# NewBee.net
KiCad netlist of a schematic drawn in Altium Designer
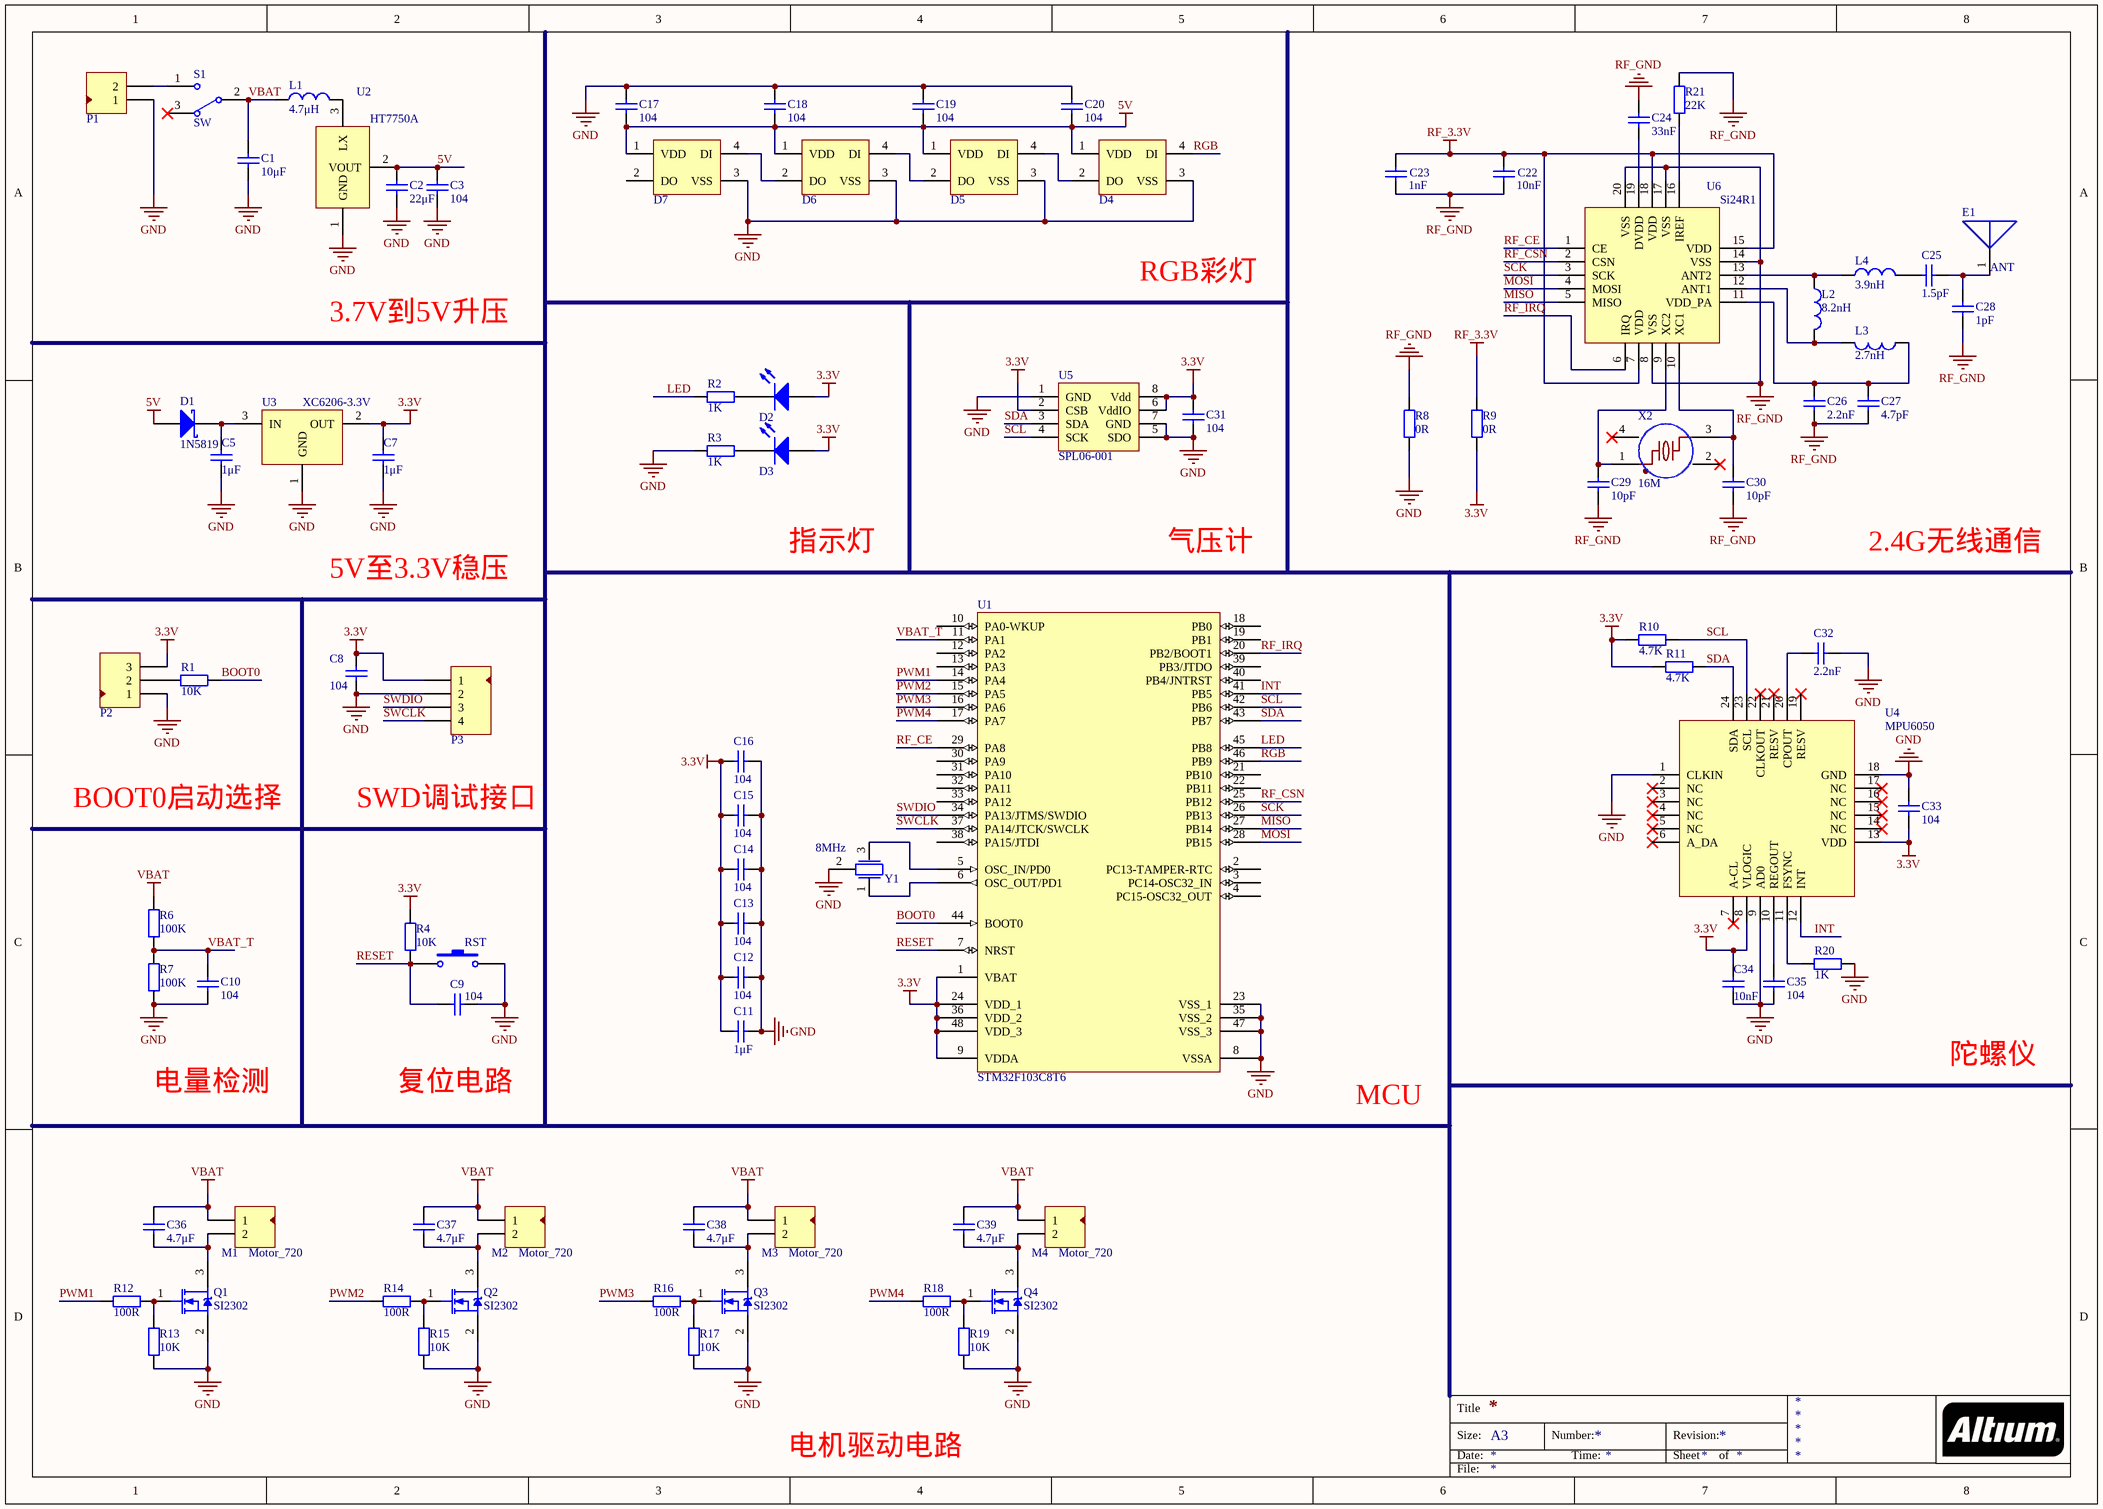
[diagram p0: NewBee.SchDoc]

(export (version "E")
  (design (tool "Eeschema 10.0.6"))
  (components
    (comp (ref "C1")
      (value "10μF")
      (footprint "C-0603")
      (description "贴片瓷片电容")
      (fields (field (name "PUBLISHER") "Altium Limited"))
      (libsource (lib "ChunLee") (part "Cap-S"))
    )
    (comp (ref "C2")
      (value "22μF")
      (footprint "C-0603")
      (description "贴片瓷片电容")
      (fields (field (name "PUBLISHER") "Altium Limited"))
      (libsource (lib "ChunLee") (part "Cap-S"))
    )
    (comp (ref "C3")
      (value "104")
      (footprint "C-0603")
      (description "贴片瓷片电容")
      (fields (field (name "PUBLISHER") "Altium Limited"))
      (libsource (lib "ChunLee") (part "Cap-S"))
    )
    (comp (ref "C5")
      (value "1μF")
      (footprint "C-0603")
      (description "贴片瓷片电容")
      (fields (field (name "PUBLISHER") "Altium Limited"))
      (libsource (lib "ChunLee") (part "Cap-S"))
    )
    (comp (ref "C7")
      (value "1μF")
      (footprint "C-0603")
      (description "贴片瓷片电容")
      (fields (field (name "PUBLISHER") "Altium Limited"))
      (libsource (lib "ChunLee") (part "Cap-S"))
    )
    (comp (ref "C8")
      (value "104")
      (footprint "C-0603")
      (description "贴片瓷片电容")
      (fields (field (name "PUBLISHER") "Altium Limited"))
      (libsource (lib "ChunLee") (part "Cap-S"))
    )
    (comp (ref "C9")
      (value "104")
      (footprint "C-0603")
      (description "贴片瓷片电容")
      (fields (field (name "PUBLISHER") "Altium Limited"))
      (libsource (lib "ChunLee") (part "Cap-S"))
    )
    (comp (ref "C10")
      (value "104")
      (footprint "C-0603")
      (description "贴片瓷片电容")
      (fields (field (name "PUBLISHER") "Altium Limited"))
      (libsource (lib "ChunLee") (part "Cap-S"))
    )
    (comp (ref "C11")
      (value "1μF")
      (footprint "C-0603")
      (description "贴片瓷片电容")
      (fields (field (name "PUBLISHER") "Altium Limited"))
      (libsource (lib "ChunLee") (part "Cap-S"))
    )
    (comp (ref "C12")
      (value "104")
      (footprint "C-0603")
      (description "贴片瓷片电容")
      (fields (field (name "PUBLISHER") "Altium Limited"))
      (libsource (lib "ChunLee") (part "Cap-S"))
    )
    (comp (ref "C13")
      (value "104")
      (footprint "C-0603")
      (description "贴片瓷片电容")
      (fields (field (name "PUBLISHER") "Altium Limited"))
      (libsource (lib "ChunLee") (part "Cap-S"))
    )
    (comp (ref "C14")
      (value "104")
      (footprint "C-0603")
      (description "贴片瓷片电容")
      (fields (field (name "PUBLISHER") "Altium Limited"))
      (libsource (lib "ChunLee") (part "Cap-S"))
    )
    (comp (ref "C15")
      (value "104")
      (footprint "C-0603")
      (description "贴片瓷片电容")
      (fields (field (name "PUBLISHER") "Altium Limited"))
      (libsource (lib "ChunLee") (part "Cap-S"))
    )
    (comp (ref "C16")
      (value "104")
      (footprint "C-0603")
      (description "贴片瓷片电容")
      (fields (field (name "PUBLISHER") "Altium Limited"))
      (libsource (lib "ChunLee") (part "Cap-S"))
    )
    (comp (ref "C17")
      (value "104")
      (footprint "C-0603")
      (description "贴片瓷片电容")
      (fields (field (name "PUBLISHER") "Altium Limited"))
      (libsource (lib "ChunLee") (part "Cap-S"))
    )
    (comp (ref "C18")
      (value "104")
      (footprint "C-0603")
      (description "贴片瓷片电容")
      (fields (field (name "PUBLISHER") "Altium Limited"))
      (libsource (lib "ChunLee") (part "Cap-S"))
    )
    (comp (ref "C19")
      (value "104")
      (footprint "C-0603")
      (description "贴片瓷片电容")
      (fields (field (name "PUBLISHER") "Altium Limited"))
      (libsource (lib "ChunLee") (part "Cap-S"))
    )
    (comp (ref "C20")
      (value "104")
      (footprint "C-0603")
      (description "贴片瓷片电容")
      (fields (field (name "PUBLISHER") "Altium Limited"))
      (libsource (lib "ChunLee") (part "Cap-S"))
    )
    (comp (ref "C22")
      (value "10nF")
      (footprint "C-0603")
      (description "贴片瓷片电容")
      (fields (field (name "PUBLISHER") "Altium Limited"))
      (libsource (lib "ChunLee") (part "Cap-S"))
    )
    (comp (ref "C23")
      (value "1nF")
      (footprint "C-0603")
      (description "贴片瓷片电容")
      (fields (field (name "PUBLISHER") "Altium Limited"))
      (libsource (lib "ChunLee") (part "Cap-S"))
    )
    (comp (ref "C24")
      (value "33nF")
      (footprint "C-0603")
      (description "贴片瓷片电容")
      (fields (field (name "PUBLISHER") "Altium Limited"))
      (libsource (lib "ChunLee") (part "Cap-S"))
    )
    (comp (ref "C25")
      (value "1.5pF")
      (footprint "C-0603")
      (description "贴片瓷片电容")
      (fields (field (name "PUBLISHER") "Altium Limited"))
      (libsource (lib "ChunLee") (part "Cap-S"))
    )
    (comp (ref "C26")
      (value "2.2nF")
      (footprint "C-0603")
      (description "贴片瓷片电容")
      (fields (field (name "PUBLISHER") "Altium Limited"))
      (libsource (lib "ChunLee") (part "Cap-S"))
    )
    (comp (ref "C27")
      (value "4.7pF")
      (footprint "C-0603")
      (description "贴片瓷片电容")
      (fields (field (name "PUBLISHER") "Altium Limited"))
      (libsource (lib "ChunLee") (part "Cap-S"))
    )
    (comp (ref "C28")
      (value "1pF")
      (footprint "C-0603")
      (description "贴片瓷片电容")
      (fields (field (name "PUBLISHER") "Altium Limited"))
      (libsource (lib "ChunLee") (part "Cap-S"))
    )
    (comp (ref "C29")
      (value "10pF")
      (footprint "C-0603")
      (description "贴片瓷片电容")
      (fields (field (name "PUBLISHER") "Altium Limited"))
      (libsource (lib "ChunLee") (part "Cap-S"))
    )
    (comp (ref "C30")
      (value "10pF")
      (footprint "C-0603")
      (description "贴片瓷片电容")
      (fields (field (name "PUBLISHER") "Altium Limited"))
      (libsource (lib "ChunLee") (part "Cap-S"))
    )
    (comp (ref "C31")
      (value "104")
      (footprint "C-0603")
      (description "贴片瓷片电容")
      (fields (field (name "PUBLISHER") "Altium Limited"))
      (libsource (lib "ChunLee") (part "Cap-S"))
    )
    (comp (ref "C32")
      (value "2.2nF")
      (footprint "C-0603")
      (description "贴片瓷片电容")
      (fields (field (name "PUBLISHER") "Altium Limited"))
      (libsource (lib "ChunLee") (part "Cap-S"))
    )
    (comp (ref "C33")
      (value "104")
      (footprint "C-0603")
      (description "贴片瓷片电容")
      (fields (field (name "PUBLISHER") "Altium Limited"))
      (libsource (lib "ChunLee") (part "Cap-S"))
    )
    (comp (ref "C34")
      (value "10nF")
      (footprint "C-0603")
      (description "贴片瓷片电容")
      (fields (field (name "PUBLISHER") "Altium Limited"))
      (libsource (lib "ChunLee") (part "Cap-S"))
    )
    (comp (ref "C35")
      (value "104")
      (footprint "C-0603")
      (description "贴片瓷片电容")
      (fields (field (name "PUBLISHER") "Altium Limited"))
      (libsource (lib "ChunLee") (part "Cap-S"))
    )
    (comp (ref "C36")
      (value "4.7μF")
      (footprint "C-0603")
      (description "贴片瓷片电容")
      (fields (field (name "PUBLISHER") "Altium Limited"))
      (libsource (lib "ChunLee") (part "Cap-S"))
    )
    (comp (ref "C37")
      (value "4.7μF")
      (footprint "C-0603")
      (description "贴片瓷片电容")
      (fields (field (name "PUBLISHER") "Altium Limited"))
      (libsource (lib "ChunLee") (part "Cap-S"))
    )
    (comp (ref "C38")
      (value "4.7μF")
      (footprint "C-0603")
      (description "贴片瓷片电容")
      (fields (field (name "PUBLISHER") "Altium Limited"))
      (libsource (lib "ChunLee") (part "Cap-S"))
    )
    (comp (ref "C39")
      (value "4.7μF")
      (footprint "C-0603")
      (description "贴片瓷片电容")
      (fields (field (name "PUBLISHER") "Altium Limited"))
      (libsource (lib "ChunLee") (part "Cap-S"))
    )
    (comp (ref "D1")
      (value "1N5819")
      (footprint "SOD-323_L1.6-W1.3-LS2.7-RD")
      (description "肖特基二极管")
      (fields (field (name "TYPE") "1N5819") (field (name "PUBLISHER") "Altium Limited"))
      (libsource (lib "ChunLee") (part "Diode-Schottky"))
    )
    (comp (ref "D2")
      (value "LED0")
      (footprint "LED-0805")
      (description "发光二极管")
      (fields (field (name "PUBLISHER") "Altium Limited"))
      (libsource (lib "ChunLee") (part "LED0"))
    )
    (comp (ref "D3")
      (value "LED0")
      (footprint "LED-0805")
      (description "发光二极管")
      (fields (field (name "PUBLISHER") "Altium Limited"))
      (libsource (lib "ChunLee") (part "LED0"))
    )
    (comp (ref "D4")
      (value "WS2812B")
      (footprint "SMD-5050-4")
      (description "WS2812B 4脚RGB全彩LED")
      (libsource (lib "ChunLee") (part "WS2812B"))
    )
    (comp (ref "D5")
      (value "WS2812B")
      (footprint "SMD-5050-4")
      (description "WS2812B 4脚RGB全彩LED")
      (libsource (lib "ChunLee") (part "WS2812B"))
    )
    (comp (ref "D6")
      (value "WS2812B")
      (footprint "SMD-5050-4")
      (description "WS2812B 4脚RGB全彩LED")
      (libsource (lib "ChunLee") (part "WS2812B"))
    )
    (comp (ref "D7")
      (value "WS2812B")
      (footprint "SMD-5050-4")
      (description "WS2812B 4脚RGB全彩LED")
      (libsource (lib "ChunLee") (part "WS2812B"))
    )
    (comp (ref "E1")
      (value "ANT")
      (footprint "NewBee_PcbLib:AN3216")
      (description "2.4G Antenna")
      (fields (field (name "PUBLISHER") "mazhongwei"))
      (libsource (lib "NewBee_Schlib") (part "ANT"))
    )
    (comp (ref "L1")
      (value "4.7μH")
      (footprint "1210")
      (description "电感")
      (fields (field (name "Comment") "Inductor") (field (name "PUBLISHER") "Altium Limited"))
      (libsource (lib "ChunLee") (part "Inductor"))
    )
    (comp (ref "L2")
      (value "8.2nH")
      (footprint "0603-1")
      (description "电感")
      (fields (field (name "Comment") "Inductor") (field (name "PUBLISHER") "Altium Limited"))
      (libsource (lib "ChunLee") (part "Inductor"))
    )
    (comp (ref "L3")
      (value "2.7nH")
      (footprint "0603-1")
      (description "电感")
      (fields (field (name "Comment") "Inductor") (field (name "PUBLISHER") "Altium Limited"))
      (libsource (lib "ChunLee") (part "Inductor"))
    )
    (comp (ref "L4")
      (value "3.9nH")
      (footprint "0603-1")
      (description "电感")
      (fields (field (name "Comment") "Inductor") (field (name "PUBLISHER") "Altium Limited"))
      (libsource (lib "ChunLee") (part "Inductor"))
    )
    (comp (ref "M1")
      (value "Motor_720")
      (footprint "PH2.0-2P-TH")
      (description "接插件")
      (fields (field (name "PUBLISHER") "Altium Limited"))
      (libsource (lib "HDR_ChunLee") (part "Header 2"))
    )
    (comp (ref "M2")
      (value "Motor_720")
      (footprint "PH2.0-2P-TH")
      (description "接插件")
      (fields (field (name "PUBLISHER") "Altium Limited"))
      (libsource (lib "HDR_ChunLee") (part "Header 2"))
    )
    (comp (ref "M3")
      (value "Motor_720")
      (footprint "PH2.0-2P-TH")
      (description "接插件")
      (fields (field (name "PUBLISHER") "Altium Limited"))
      (libsource (lib "HDR_ChunLee") (part "Header 2"))
    )
    (comp (ref "M4")
      (value "Motor_720")
      (footprint "PH2.0-2P-TH")
      (description "接插件")
      (fields (field (name "PUBLISHER") "Altium Limited"))
      (libsource (lib "HDR_ChunLee") (part "Header 2"))
    )
    (comp (ref "P1")
      (value "Header 2")
      (footprint "PH2.0-2P-SMD-WT")
      (description "接插件")
      (fields (field (name "PUBLISHER") "Altium Limited"))
      (libsource (lib "") (part "Header 2_1"))
    )
    (comp (ref "P2")
      (value "Header 3")
      (footprint "HDR3X1-2.54")
      (description "接插件")
      (fields (field (name "PUBLISHER") "Altium Limited"))
      (libsource (lib "HDR_ChunLee") (part "Header 3"))
    )
    (comp (ref "P3")
      (value "Header 4")
      (footprint "HDR4X1-2.54")
      (description "接插件")
      (fields (field (name "PUBLISHER") "Altium Limited"))
      (libsource (lib "HDR_ChunLee") (part "Header 4"))
    )
    (comp (ref "Q1")
      (value "SI2302")
      (footprint "SOT23-3")
      (description "N沟道贴片")
      (fields (field (name "PUBLISHER") "Altium Limited"))
      (libsource (lib "ChunLee") (part "SI2302"))
    )
    (comp (ref "Q2")
      (value "SI2302")
      (footprint "SOT23-3")
      (description "N沟道贴片")
      (fields (field (name "PUBLISHER") "Altium Limited"))
      (libsource (lib "ChunLee") (part "SI2302"))
    )
    (comp (ref "Q3")
      (value "SI2302")
      (footprint "SOT23-3")
      (description "N沟道贴片")
      (fields (field (name "PUBLISHER") "Altium Limited"))
      (libsource (lib "ChunLee") (part "SI2302"))
    )
    (comp (ref "Q4")
      (value "SI2302")
      (footprint "SOT23-3")
      (description "N沟道贴片")
      (fields (field (name "PUBLISHER") "Altium Limited"))
      (libsource (lib "ChunLee") (part "SI2302"))
    )
    (comp (ref "R1")
      (value "10K")
      (footprint "0603-1")
      (description "贴片电阻")
      (fields (field (name "PUBLISHER") "Altium Limited"))
      (libsource (lib "") (part "Res1_3"))
    )
    (comp (ref "R2")
      (value "1K")
      (footprint "0603-1")
      (description "贴片电阻")
      (fields (field (name "PUBLISHER") "Altium Limited"))
      (libsource (lib "") (part "Res1_2"))
    )
    (comp (ref "R3")
      (value "1K")
      (footprint "0603-1")
      (description "贴片电阻")
      (fields (field (name "PUBLISHER") "Altium Limited"))
      (libsource (lib "") (part "Res1_2"))
    )
    (comp (ref "R4")
      (value "10K")
      (footprint "0603-1")
      (description "贴片电阻")
      (fields (field (name "PUBLISHER") "Altium Limited"))
      (libsource (lib "ChunLee") (part "Res1"))
    )
    (comp (ref "R6")
      (value "100K")
      (footprint "0603-1")
      (description "贴片电阻")
      (fields (field (name "PUBLISHER") "Altium Limited"))
      (libsource (lib "") (part "Res1_1"))
    )
    (comp (ref "R7")
      (value "100K")
      (footprint "0603-1")
      (description "贴片电阻")
      (fields (field (name "PUBLISHER") "Altium Limited"))
      (libsource (lib "") (part "Res1_1"))
    )
    (comp (ref "R8")
      (value "0R")
      (footprint "0603-1")
      (description "贴片电阻")
      (fields (field (name "PUBLISHER") "Altium Limited"))
      (libsource (lib "") (part "Res1_1"))
    )
    (comp (ref "R9")
      (value "0R")
      (footprint "0603-1")
      (description "贴片电阻")
      (fields (field (name "PUBLISHER") "Altium Limited"))
      (libsource (lib "") (part "Res1_1"))
    )
    (comp (ref "R10")
      (value "4.7K")
      (footprint "0603-1")
      (description "贴片电阻")
      (fields (field (name "PUBLISHER") "Altium Limited"))
      (libsource (lib "") (part "Res1_2"))
    )
    (comp (ref "R11")
      (value "4.7K")
      (footprint "0603-1")
      (description "贴片电阻")
      (fields (field (name "PUBLISHER") "Altium Limited"))
      (libsource (lib "") (part "Res1_2"))
    )
    (comp (ref "R12")
      (value "100R")
      (footprint "0603-1")
      (description "贴片电阻")
      (fields (field (name "PUBLISHER") "Altium Limited"))
      (libsource (lib "") (part "Res1_2"))
    )
    (comp (ref "R13")
      (value "10K")
      (footprint "0603-1")
      (description "贴片电阻")
      (fields (field (name "PUBLISHER") "Altium Limited"))
      (libsource (lib "ChunLee") (part "Res1"))
    )
    (comp (ref "R14")
      (value "100R")
      (footprint "0603-1")
      (description "贴片电阻")
      (fields (field (name "PUBLISHER") "Altium Limited"))
      (libsource (lib "") (part "Res1_2"))
    )
    (comp (ref "R15")
      (value "10K")
      (footprint "0603-1")
      (description "贴片电阻")
      (fields (field (name "PUBLISHER") "Altium Limited"))
      (libsource (lib "ChunLee") (part "Res1"))
    )
    (comp (ref "R16")
      (value "100R")
      (footprint "0603-1")
      (description "贴片电阻")
      (fields (field (name "PUBLISHER") "Altium Limited"))
      (libsource (lib "") (part "Res1_2"))
    )
    (comp (ref "R17")
      (value "10K")
      (footprint "0603-1")
      (description "贴片电阻")
      (fields (field (name "PUBLISHER") "Altium Limited"))
      (libsource (lib "ChunLee") (part "Res1"))
    )
    (comp (ref "R18")
      (value "100R")
      (footprint "0603-1")
      (description "贴片电阻")
      (fields (field (name "PUBLISHER") "Altium Limited"))
      (libsource (lib "") (part "Res1_2"))
    )
    (comp (ref "R19")
      (value "10K")
      (footprint "0603-1")
      (description "贴片电阻")
      (fields (field (name "PUBLISHER") "Altium Limited"))
      (libsource (lib "ChunLee") (part "Res1"))
    )
    (comp (ref "R20")
      (value "1K")
      (footprint "0603-1")
      (description "贴片电阻")
      (fields (field (name "PUBLISHER") "Altium Limited"))
      (libsource (lib "") (part "Res1_3"))
    )
    (comp (ref "R21")
      (value "22K")
      (footprint "0603-1")
      (description "贴片电阻")
      (fields (field (name "PUBLISHER") "Altium Limited"))
      (libsource (lib "ChunLee") (part "Res1"))
    )
    (comp (ref "RST")
      (value "SW-PB")
      (footprint "SW_PB2_A1")
      (description "微动开关")
      (fields (field (name "PUBLISHER") "Altium Limited"))
      (libsource (lib "ChunLee") (part "SW-PB"))
    )
    (comp (ref "S1")
      (value "SW")
      (footprint "SW-SMD_DEALON_MK-12D04-G2")
      (description "开关")
      (fields (field (name "PUBLISHER") "Altium Limited"))
      (libsource (lib "ChunLee") (part "SW-SPDT"))
    )
    (comp (ref "U1")
      (value "STM32F103C8T6")
      (footprint "LQFP-48")
      (description "STM32F103, 48引脚, 64Kb Flash, 20Kb SRAM")
      (fields (field (name "PUBLISHER") "Altium Limited"))
      (libsource (lib "ChunLee") (part "STM32F103C8T6"))
    )
    (comp (ref "U2")
      (value "HT7750A")
      (footprint "SOT-89-3_L4.5-W2.5-P1.50-LS4.2-BR")
      (libsource (lib "ChunLee") (part "HT7750SA_SOT89"))
    )
    (comp (ref "U3")
      (value "XC6206-3.3V")
      (footprint "SOT23-3")
      (description "稳压芯片")
      (libsource (lib "ChunLee") (part "XC6206"))
    )
    (comp (ref "U4")
      (value "MPU6050")
      (footprint "QFN-24_4x4x05P")
      (libsource (lib "NewBee_Schlib") (part "MPU6050"))
    )
    (comp (ref "U5")
      (value "SPL06-001")
      (footprint "SENSOR-SMD_SPL06-001")
      (description "气压计")
      (fields (field (name "PUBLISHER") "mazhongwei"))
      (libsource (lib "NewBee_Schlib") (part "FBM320"))
    )
    (comp (ref "U6") (value "Si24R1") (footprint "QFN20") (libsource (lib "NewBee_Schlib") (part "nRF24L01")))
    (comp (ref "X2")
      (value "16M")
      (footprint "X-SMD_4P-L3.2-W2.5-BL")
      (libsource (lib "ChunLee") (part "XTAL-4PIN"))
    )
    (comp (ref "Y1")
      (value "8MHz")
      (footprint "OSC-SMD_3P-L3.2-W1.3-P1.20-L")
      (description "贴片晶振")
      (libsource (lib "ChunLee") (part "XTAL-3PIN"))
    )
  )
  (nets
    (net (code "1") (name "/BOOT0") (class "Default")
      (node (ref "R1") (pin "1") (pinfunction "1_1") (pintype "passive"))
      (node (ref "U1") (pin "44") (pinfunction "BOOT0_44") (pintype "input"))
    )
    (net (code "2") (name "/INT") (class "Default")
      (node (ref "U1") (pin "41") (pinfunction "PB5_41") (pintype "bidirectional"))
      (node (ref "U4") (pin "12") (pinfunction "INT_12") (pintype "passive"))
    )
    (net (code "3") (name "/LED") (class "Default")
      (node (ref "R2") (pin "1") (pinfunction "1_1") (pintype "passive"))
      (node (ref "U1") (pin "45") (pinfunction "PB8_45") (pintype "bidirectional"))
    )
    (net (code "4") (name "/MISO") (class "Default")
      (node (ref "U1") (pin "27") (pinfunction "PB14_27") (pintype "bidirectional"))
      (node (ref "U6") (pin "5") (pinfunction "MISO_5") (pintype "passive"))
    )
    (net (code "5") (name "/MOSI") (class "Default")
      (node (ref "U1") (pin "28") (pinfunction "PB15_28") (pintype "bidirectional"))
      (node (ref "U6") (pin "4") (pinfunction "MOSI_4") (pintype "passive"))
    )
    (net (code "6") (name "/PWM1") (class "Default")
      (node (ref "R12") (pin "1") (pinfunction "1_1") (pintype "passive"))
      (node (ref "U1") (pin "14") (pinfunction "PA4_14") (pintype "bidirectional"))
    )
    (net (code "7") (name "/PWM2") (class "Default")
      (node (ref "R14") (pin "1") (pinfunction "1_1") (pintype "passive"))
      (node (ref "U1") (pin "15") (pinfunction "PA5_15") (pintype "bidirectional"))
    )
    (net (code "8") (name "/PWM3") (class "Default")
      (node (ref "R16") (pin "1") (pinfunction "1_1") (pintype "passive"))
      (node (ref "U1") (pin "16") (pinfunction "PA6_16") (pintype "bidirectional"))
    )
    (net (code "9") (name "/PWM4") (class "Default")
      (node (ref "R18") (pin "1") (pinfunction "1_1") (pintype "passive"))
      (node (ref "U1") (pin "17") (pinfunction "PA7_17") (pintype "bidirectional"))
    )
    (net (code "10") (name "/RESET") (class "Default")
      (node (ref "C9") (pin "1") (pinfunction "1_1") (pintype "passive"))
      (node (ref "R4") (pin "1") (pinfunction "1_1") (pintype "passive"))
      (node (ref "RST") (pin "1") (pinfunction "1_1") (pintype "passive"))
      (node (ref "U1") (pin "7") (pinfunction "NRST_7") (pintype "bidirectional"))
    )
    (net (code "11") (name "/RF_CE") (class "Default")
      (node (ref "U1") (pin "29") (pinfunction "PA8_29") (pintype "bidirectional"))
      (node (ref "U6") (pin "1") (pinfunction "CE_1") (pintype "passive"))
    )
    (net (code "12") (name "/RF_CSN") (class "Default")
      (node (ref "U1") (pin "25") (pinfunction "PB12_25") (pintype "bidirectional"))
      (node (ref "U6") (pin "2") (pinfunction "CSN_2") (pintype "passive"))
    )
    (net (code "13") (name "/RF_IRQ") (class "Default")
      (node (ref "U1") (pin "20") (pinfunction "PB2/BOOT1_20") (pintype "bidirectional"))
      (node (ref "U6") (pin "6") (pinfunction "IRQ_6") (pintype "passive"))
    )
    (net (code "14") (name "/RGB") (class "Default")
      (node (ref "D4") (pin "4") (pinfunction "DI_4") (pintype "passive"))
      (node (ref "U1") (pin "46") (pinfunction "PB9_46") (pintype "bidirectional"))
    )
    (net (code "15") (name "/SCK") (class "Default")
      (node (ref "U1") (pin "26") (pinfunction "PB13_26") (pintype "bidirectional"))
      (node (ref "U6") (pin "3") (pinfunction "SCK_3") (pintype "passive"))
    )
    (net (code "16") (name "/SCL") (class "Default")
      (node (ref "R10") (pin "2") (pinfunction "2_2") (pintype "passive"))
      (node (ref "U1") (pin "42") (pinfunction "PB6_42") (pintype "bidirectional"))
      (node (ref "U4") (pin "23") (pinfunction "SCL_23") (pintype "passive"))
      (node (ref "U5") (pin "4") (pinfunction "SCK_4") (pintype "passive"))
    )
    (net (code "17") (name "/SDA") (class "Default")
      (node (ref "R11") (pin "2") (pinfunction "2_2") (pintype "passive"))
      (node (ref "U1") (pin "43") (pinfunction "PB7_43") (pintype "bidirectional"))
      (node (ref "U4") (pin "24") (pinfunction "SDA_24") (pintype "passive"))
      (node (ref "U5") (pin "3") (pinfunction "SDA_3") (pintype "passive"))
    )
    (net (code "18") (name "/SWCLK") (class "Default")
      (node (ref "P3") (pin "4") (pinfunction "4_4") (pintype "passive"))
      (node (ref "U1") (pin "37") (pinfunction "PA14/JTCK/SWCLK_37") (pintype "bidirectional"))
    )
    (net (code "19") (name "/SWDIO") (class "Default")
      (node (ref "P3") (pin "3") (pinfunction "3_3") (pintype "passive"))
      (node (ref "U1") (pin "34") (pinfunction "PA13/JTMS/SWDIO_34") (pintype "bidirectional"))
    )
    (net (code "20") (name "/VBAT_T") (class "Default")
      (node (ref "C10") (pin "2") (pinfunction "2_2") (pintype "passive"))
      (node (ref "R6") (pin "2") (pinfunction "2_2") (pintype "passive"))
      (node (ref "R7") (pin "1") (pinfunction "1_1") (pintype "passive"))
      (node (ref "U1") (pin "11") (pinfunction "PA1_11") (pintype "bidirectional"))
    )
    (net (code "21") (name "3.3V") (class "Default")
      (node (ref "C11") (pin "2") (pinfunction "2_2") (pintype "passive"))
      (node (ref "C12") (pin "2") (pinfunction "2_2") (pintype "passive"))
      (node (ref "C13") (pin "2") (pinfunction "2_2") (pintype "passive"))
      (node (ref "C14") (pin "1") (pinfunction "1_1") (pintype "passive"))
      (node (ref "C15") (pin "2") (pinfunction "2_2") (pintype "passive"))
      (node (ref "C16") (pin "2") (pinfunction "2_2") (pintype "passive"))
      (node (ref "C31") (pin "2") (pinfunction "2_2") (pintype "passive"))
      (node (ref "C33") (pin "2") (pinfunction "2_2") (pintype "passive"))
      (node (ref "C34") (pin "2") (pinfunction "2_2") (pintype "passive"))
      (node (ref "C7") (pin "1") (pinfunction "1_1") (pintype "passive"))
      (node (ref "C8") (pin "1") (pinfunction "1_1") (pintype "passive"))
      (node (ref "D2") (pin "1") (pinfunction "A_1") (pintype "passive"))
      (node (ref "D3") (pin "1") (pinfunction "A_1") (pintype "passive"))
      (node (ref "P2") (pin "3") (pinfunction "3_3") (pintype "passive"))
      (node (ref "P3") (pin "1") (pinfunction "1_1") (pintype "passive"))
      (node (ref "R10") (pin "1") (pinfunction "1_1") (pintype "passive"))
      (node (ref "R11") (pin "1") (pinfunction "1_1") (pintype "passive"))
      (node (ref "R4") (pin "2") (pinfunction "2_2") (pintype "passive"))
      (node (ref "R9") (pin "2") (pinfunction "2_2") (pintype "passive"))
      (node (ref "U1") (pin "1") (pinfunction "VBAT_1") (pintype "power_in"))
      (node (ref "U1") (pin "24") (pinfunction "VDD_1_24") (pintype "power_in"))
      (node (ref "U1") (pin "36") (pinfunction "VDD_2_36") (pintype "power_in"))
      (node (ref "U1") (pin "48") (pinfunction "VDD_3_48") (pintype "power_in"))
      (node (ref "U1") (pin "9") (pinfunction "VDDA_9") (pintype "power_in"))
      (node (ref "U3") (pin "2") (pinfunction "OUT_2") (pintype "passive"))
      (node (ref "U4") (pin "13") (pinfunction "VDD_13") (pintype "passive"))
      (node (ref "U4") (pin "8") (pinfunction "VLOGIC_8") (pintype "passive"))
      (node (ref "U5") (pin "2") (pinfunction "CSB_2") (pintype "passive"))
      (node (ref "U5") (pin "6") (pinfunction "VddIO_6") (pintype "passive"))
      (node (ref "U5") (pin "8") (pinfunction "Vdd_8") (pintype "passive"))
    )
    (net (code "22") (name "5V") (class "Default")
      (node (ref "C17") (pin "1") (pinfunction "1_1") (pintype "passive"))
      (node (ref "C18") (pin "1") (pinfunction "1_1") (pintype "passive"))
      (node (ref "C19") (pin "1") (pinfunction "1_1") (pintype "passive"))
      (node (ref "C2") (pin "2") (pinfunction "2_2") (pintype "passive"))
      (node (ref "C20") (pin "1") (pinfunction "1_1") (pintype "passive"))
      (node (ref "C3") (pin "2") (pinfunction "2_2") (pintype "passive"))
      (node (ref "D1") (pin "1") (pinfunction "A_1") (pintype "passive"))
      (node (ref "D4") (pin "1") (pinfunction "VDD_1") (pintype "passive"))
      (node (ref "D5") (pin "1") (pinfunction "VDD_1") (pintype "passive"))
      (node (ref "D6") (pin "1") (pinfunction "VDD_1") (pintype "passive"))
      (node (ref "D7") (pin "1") (pinfunction "VDD_1") (pintype "passive"))
      (node (ref "U2") (pin "2") (pinfunction "VOUT_2") (pintype "passive"))
    )
    (net (code "23") (name "GND") (class "Default")
      (node (ref "C1") (pin "1") (pinfunction "1_1") (pintype "passive"))
      (node (ref "C10") (pin "1") (pinfunction "1_1") (pintype "passive"))
      (node (ref "C11") (pin "1") (pinfunction "1_1") (pintype "passive"))
      (node (ref "C12") (pin "1") (pinfunction "1_1") (pintype "passive"))
      (node (ref "C13") (pin "1") (pinfunction "1_1") (pintype "passive"))
      (node (ref "C14") (pin "2") (pinfunction "2_2") (pintype "passive"))
      (node (ref "C15") (pin "1") (pinfunction "1_1") (pintype "passive"))
      (node (ref "C16") (pin "1") (pinfunction "1_1") (pintype "passive"))
      (node (ref "C17") (pin "2") (pinfunction "2_2") (pintype "passive"))
      (node (ref "C18") (pin "2") (pinfunction "2_2") (pintype "passive"))
      (node (ref "C19") (pin "2") (pinfunction "2_2") (pintype "passive"))
      (node (ref "C2") (pin "1") (pinfunction "1_1") (pintype "passive"))
      (node (ref "C20") (pin "2") (pinfunction "2_2") (pintype "passive"))
      (node (ref "C3") (pin "1") (pinfunction "1_1") (pintype "passive"))
      (node (ref "C31") (pin "1") (pinfunction "1_1") (pintype "passive"))
      (node (ref "C32") (pin "1") (pinfunction "1_1") (pintype "passive"))
      (node (ref "C33") (pin "1") (pinfunction "1_1") (pintype "passive"))
      (node (ref "C34") (pin "1") (pinfunction "1_1") (pintype "passive"))
      (node (ref "C35") (pin "2") (pinfunction "2_2") (pintype "passive"))
      (node (ref "C5") (pin "2") (pinfunction "2_2") (pintype "passive"))
      (node (ref "C7") (pin "2") (pinfunction "2_2") (pintype "passive"))
      (node (ref "C8") (pin "2") (pinfunction "2_2") (pintype "passive"))
      (node (ref "C9") (pin "2") (pinfunction "2_2") (pintype "passive"))
      (node (ref "D4") (pin "3") (pinfunction "VSS_3") (pintype "passive"))
      (node (ref "D5") (pin "3") (pinfunction "VSS_3") (pintype "passive"))
      (node (ref "D6") (pin "3") (pinfunction "VSS_3") (pintype "passive"))
      (node (ref "D7") (pin "3") (pinfunction "VSS_3") (pintype "passive"))
      (node (ref "P1") (pin "1") (pinfunction "1_1") (pintype "passive"))
      (node (ref "P2") (pin "1") (pinfunction "1_1") (pintype "passive"))
      (node (ref "P3") (pin "2") (pinfunction "2_2") (pintype "passive"))
      (node (ref "Q1") (pin "2") (pinfunction "S_2") (pintype "passive"))
      (node (ref "Q2") (pin "2") (pinfunction "S_2") (pintype "passive"))
      (node (ref "Q3") (pin "2") (pinfunction "S_2") (pintype "passive"))
      (node (ref "Q4") (pin "2") (pinfunction "S_2") (pintype "passive"))
      (node (ref "R13") (pin "1") (pinfunction "1_1") (pintype "passive"))
      (node (ref "R15") (pin "1") (pinfunction "1_1") (pintype "passive"))
      (node (ref "R17") (pin "1") (pinfunction "1_1") (pintype "passive"))
      (node (ref "R19") (pin "1") (pinfunction "1_1") (pintype "passive"))
      (node (ref "R20") (pin "1") (pinfunction "1_1") (pintype "passive"))
      (node (ref "R3") (pin "1") (pinfunction "1_1") (pintype "passive"))
      (node (ref "R7") (pin "2") (pinfunction "2_2") (pintype "passive"))
      (node (ref "R8") (pin "2") (pinfunction "2_2") (pintype "passive"))
      (node (ref "RST") (pin "2") (pinfunction "2_2") (pintype "passive"))
      (node (ref "U1") (pin "23") (pinfunction "VSS_1_23") (pintype "power_in"))
      (node (ref "U1") (pin "35") (pinfunction "VSS_2_35") (pintype "power_in"))
      (node (ref "U1") (pin "47") (pinfunction "VSS_3_47") (pintype "power_in"))
      (node (ref "U1") (pin "8") (pinfunction "VSSA_8") (pintype "power_in"))
      (node (ref "U2") (pin "1") (pinfunction "GND_1") (pintype "passive"))
      (node (ref "U3") (pin "1") (pinfunction "GND_1") (pintype "passive"))
      (node (ref "U4") (pin "1") (pinfunction "CLKIN_1") (pintype "passive"))
      (node (ref "U4") (pin "18") (pinfunction "GND_18") (pintype "passive"))
      (node (ref "U4") (pin "9") (pinfunction "AD0_9") (pintype "passive"))
      (node (ref "U5") (pin "1") (pinfunction "GND_1") (pintype "passive"))
      (node (ref "U5") (pin "5") (pinfunction "SDO_5") (pintype "passive"))
      (node (ref "U5") (pin "7") (pinfunction "GND_7") (pintype "passive"))
      (node (ref "Y1") (pin "2") (pinfunction "2_2") (pintype "passive"))
    )
    (net (code "24") (name "Net-(C25-Pad1)") (class "Default")
      (node (ref "C25") (pin "1") (pinfunction "1_1") (pintype "passive"))
      (node (ref "C28") (pin "2") (pinfunction "2_2") (pintype "passive"))
      (node (ref "E1") (pin "1") (pinfunction "1_1") (pintype "passive"))
    )
    (net (code "25") (name "Net-(C25-Pad2)") (class "Default")
      (node (ref "C25") (pin "2") (pinfunction "2_2") (pintype "passive"))
      (node (ref "L4") (pin "2") (pinfunction "2_2") (pintype "passive"))
    )
    (net (code "26") (name "Net-(D1-K)") (class "Default")
      (node (ref "C5") (pin "1") (pinfunction "1_1") (pintype "passive"))
      (node (ref "D1") (pin "2") (pinfunction "K_2") (pintype "passive"))
      (node (ref "U3") (pin "3") (pinfunction "IN_3") (pintype "passive"))
    )
    (net (code "27") (name "Net-(D2-K)") (class "Default")
      (node (ref "D2") (pin "2") (pinfunction "K_2") (pintype "passive"))
      (node (ref "R2") (pin "2") (pinfunction "2_2") (pintype "passive"))
    )
    (net (code "28") (name "Net-(D3-K)") (class "Default")
      (node (ref "D3") (pin "2") (pinfunction "K_2") (pintype "passive"))
      (node (ref "R3") (pin "2") (pinfunction "2_2") (pintype "passive"))
    )
    (net (code "29") (name "Net-(D4-DO)") (class "Default")
      (node (ref "D4") (pin "2") (pinfunction "DO_2") (pintype "passive"))
      (node (ref "D5") (pin "4") (pinfunction "DI_4") (pintype "passive"))
    )
    (net (code "30") (name "Net-(D5-DO)") (class "Default")
      (node (ref "D5") (pin "2") (pinfunction "DO_2") (pintype "passive"))
      (node (ref "D6") (pin "4") (pinfunction "DI_4") (pintype "passive"))
    )
    (net (code "31") (name "Net-(D6-DO)") (class "Default")
      (node (ref "D6") (pin "2") (pinfunction "DO_2") (pintype "passive"))
      (node (ref "D7") (pin "4") (pinfunction "DI_4") (pintype "passive"))
    )
    (net (code "32") (name "Net-(P1-Pad2)") (class "Default")
      (node (ref "P1") (pin "2") (pinfunction "2_2") (pintype "passive"))
      (node (ref "S1") (pin "1") (pinfunction "1_1") (pintype "passive"))
    )
    (net (code "33") (name "Net-(P2-Pad2)") (class "Default")
      (node (ref "P2") (pin "2") (pinfunction "2_2") (pintype "passive"))
      (node (ref "R1") (pin "2") (pinfunction "2_2") (pintype "passive"))
    )
    (net (code "34") (name "Net-(Q1-D)") (class "Default")
      (node (ref "C36") (pin "2") (pinfunction "2_2") (pintype "passive"))
      (node (ref "M1") (pin "2") (pinfunction "2_2") (pintype "passive"))
      (node (ref "Q1") (pin "3") (pinfunction "D_3") (pintype "passive"))
    )
    (net (code "35") (name "Net-(Q1-G)") (class "Default")
      (node (ref "Q1") (pin "1") (pinfunction "G_1") (pintype "passive"))
      (node (ref "R12") (pin "2") (pinfunction "2_2") (pintype "passive"))
      (node (ref "R13") (pin "2") (pinfunction "2_2") (pintype "passive"))
    )
    (net (code "36") (name "Net-(Q2-D)") (class "Default")
      (node (ref "C37") (pin "2") (pinfunction "2_2") (pintype "passive"))
      (node (ref "M2") (pin "2") (pinfunction "2_2") (pintype "passive"))
      (node (ref "Q2") (pin "3") (pinfunction "D_3") (pintype "passive"))
    )
    (net (code "37") (name "Net-(Q2-G)") (class "Default")
      (node (ref "Q2") (pin "1") (pinfunction "G_1") (pintype "passive"))
      (node (ref "R14") (pin "2") (pinfunction "2_2") (pintype "passive"))
      (node (ref "R15") (pin "2") (pinfunction "2_2") (pintype "passive"))
    )
    (net (code "38") (name "Net-(Q3-D)") (class "Default")
      (node (ref "C38") (pin "2") (pinfunction "2_2") (pintype "passive"))
      (node (ref "M3") (pin "2") (pinfunction "2_2") (pintype "passive"))
      (node (ref "Q3") (pin "3") (pinfunction "D_3") (pintype "passive"))
    )
    (net (code "39") (name "Net-(Q3-G)") (class "Default")
      (node (ref "Q3") (pin "1") (pinfunction "G_1") (pintype "passive"))
      (node (ref "R16") (pin "2") (pinfunction "2_2") (pintype "passive"))
      (node (ref "R17") (pin "2") (pinfunction "2_2") (pintype "passive"))
    )
    (net (code "40") (name "Net-(Q4-D)") (class "Default")
      (node (ref "C39") (pin "2") (pinfunction "2_2") (pintype "passive"))
      (node (ref "M4") (pin "2") (pinfunction "2_2") (pintype "passive"))
      (node (ref "Q4") (pin "3") (pinfunction "D_3") (pintype "passive"))
    )
    (net (code "41") (name "Net-(Q4-G)") (class "Default")
      (node (ref "Q4") (pin "1") (pinfunction "G_1") (pintype "passive"))
      (node (ref "R18") (pin "2") (pinfunction "2_2") (pintype "passive"))
      (node (ref "R19") (pin "2") (pinfunction "2_2") (pintype "passive"))
    )
    (net (code "42") (name "Net-(U1-OSC_IN{slash}PD0)") (class "Default")
      (node (ref "U1") (pin "5") (pinfunction "OSC_IN/PD0_5") (pintype "input"))
      (node (ref "Y1") (pin "3") (pinfunction "3_3") (pintype "passive"))
    )
    (net (code "43") (name "Net-(U1-OSC_OUT{slash}PD1)") (class "Default")
      (node (ref "U1") (pin "6") (pinfunction "OSC_OUT/PD1_6") (pintype "output"))
      (node (ref "Y1") (pin "1") (pinfunction "1_1") (pintype "passive"))
    )
    (net (code "44") (name "Net-(U2-LX)") (class "Default")
      (node (ref "L1") (pin "2") (pinfunction "2_2") (pintype "passive"))
      (node (ref "U2") (pin "3") (pinfunction "LX_3") (pintype "passive"))
    )
    (net (code "45") (name "Net-(U4-CPOUT)") (class "Default")
      (node (ref "C32") (pin "2") (pinfunction "2_2") (pintype "passive"))
      (node (ref "U4") (pin "20") (pinfunction "CPOUT_20") (pintype "passive"))
    )
    (net (code "46") (name "Net-(U4-FSYNC)") (class "Default")
      (node (ref "R20") (pin "2") (pinfunction "2_2") (pintype "passive"))
      (node (ref "U4") (pin "11") (pinfunction "FSYNC_11") (pintype "passive"))
    )
    (net (code "47") (name "Net-(U4-REGOUT)") (class "Default")
      (node (ref "C35") (pin "1") (pinfunction "1_1") (pintype "passive"))
      (node (ref "U4") (pin "10") (pinfunction "REGOUT_10") (pintype "passive"))
    )
    (net (code "48") (name "Net-(U6-ANT1)") (class "Default")
      (node (ref "L2") (pin "2") (pinfunction "2_2") (pintype "passive"))
      (node (ref "L3") (pin "2") (pinfunction "2_2") (pintype "passive"))
      (node (ref "U6") (pin "12") (pinfunction "ANT1_12") (pintype "passive"))
    )
    (net (code "49") (name "Net-(U6-ANT2)") (class "Default")
      (node (ref "L2") (pin "1") (pinfunction "1_1") (pintype "passive"))
      (node (ref "L4") (pin "1") (pinfunction "1_1") (pintype "passive"))
      (node (ref "U6") (pin "13") (pinfunction "ANT2_13") (pintype "passive"))
    )
    (net (code "50") (name "Net-(U6-DVDD)") (class "Default")
      (node (ref "C24") (pin "1") (pinfunction "1_1") (pintype "passive"))
      (node (ref "U6") (pin "19") (pinfunction "DVDD_19") (pintype "passive"))
    )
    (net (code "51") (name "Net-(U6-IREF)") (class "Default")
      (node (ref "R21") (pin "1") (pinfunction "1_1") (pintype "passive"))
      (node (ref "U6") (pin "16") (pinfunction "IREF_16") (pintype "passive"))
    )
    (net (code "52") (name "Net-(U6-VDD_PA)") (class "Default")
      (node (ref "C26") (pin "1") (pinfunction "1_1") (pintype "passive"))
      (node (ref "C27") (pin "1") (pinfunction "1_1") (pintype "passive"))
      (node (ref "L3") (pin "1") (pinfunction "1_1") (pintype "passive"))
      (node (ref "U6") (pin "11") (pinfunction "VDD_PA_11") (pintype "passive"))
    )
    (net (code "53") (name "Net-(U6-XC1)") (class "Default")
      (node (ref "C30") (pin "2") (pinfunction "2_2") (pintype "passive"))
      (node (ref "U6") (pin "10") (pinfunction "XC1_10") (pintype "passive"))
      (node (ref "X2") (pin "3") (pinfunction "3_3") (pintype "passive"))
    )
    (net (code "54") (name "Net-(U6-XC2)") (class "Default")
      (node (ref "C29") (pin "2") (pinfunction "2_2") (pintype "passive"))
      (node (ref "U6") (pin "9") (pinfunction "XC2_9") (pintype "passive"))
      (node (ref "X2") (pin "1") (pinfunction "1_1") (pintype "passive"))
    )
    (net (code "55") (name "RF_3.3V") (class "Default")
      (node (ref "C22") (pin "2") (pinfunction "2_2") (pintype "passive"))
      (node (ref "C23") (pin "2") (pinfunction "2_2") (pintype "passive"))
      (node (ref "R9") (pin "1") (pinfunction "1_1") (pintype "passive"))
      (node (ref "U6") (pin "15") (pinfunction "VDD_15") (pintype "passive"))
      (node (ref "U6") (pin "18") (pinfunction "VDD_18") (pintype "passive"))
      (node (ref "U6") (pin "7") (pinfunction "VDD_7") (pintype "passive"))
    )
    (net (code "56") (name "RF_GND") (class "Default")
      (node (ref "C22") (pin "1") (pinfunction "1_1") (pintype "passive"))
      (node (ref "C23") (pin "1") (pinfunction "1_1") (pintype "passive"))
      (node (ref "C24") (pin "2") (pinfunction "2_2") (pintype "passive"))
      (node (ref "C26") (pin "2") (pinfunction "2_2") (pintype "passive"))
      (node (ref "C27") (pin "2") (pinfunction "2_2") (pintype "passive"))
      (node (ref "C28") (pin "1") (pinfunction "1_1") (pintype "passive"))
      (node (ref "C29") (pin "1") (pinfunction "1_1") (pintype "passive"))
      (node (ref "C30") (pin "1") (pinfunction "1_1") (pintype "passive"))
      (node (ref "R21") (pin "2") (pinfunction "2_2") (pintype "passive"))
      (node (ref "R8") (pin "1") (pinfunction "1_1") (pintype "passive"))
      (node (ref "U6") (pin "14") (pinfunction "VSS_14") (pintype "passive"))
      (node (ref "U6") (pin "17") (pinfunction "VSS_17") (pintype "passive"))
      (node (ref "U6") (pin "20") (pinfunction "VSS_20") (pintype "passive"))
      (node (ref "U6") (pin "8") (pinfunction "VSS_8") (pintype "passive"))
    )
    (net (code "57") (name "VBAT") (class "Default")
      (node (ref "C1") (pin "2") (pinfunction "2_2") (pintype "passive"))
      (node (ref "C36") (pin "1") (pinfunction "1_1") (pintype "passive"))
      (node (ref "C37") (pin "1") (pinfunction "1_1") (pintype "passive"))
      (node (ref "C38") (pin "1") (pinfunction "1_1") (pintype "passive"))
      (node (ref "C39") (pin "1") (pinfunction "1_1") (pintype "passive"))
      (node (ref "L1") (pin "1") (pinfunction "1_1") (pintype "passive"))
      (node (ref "M1") (pin "1") (pinfunction "1_1") (pintype "passive"))
      (node (ref "M2") (pin "1") (pinfunction "1_1") (pintype "passive"))
      (node (ref "M3") (pin "1") (pinfunction "1_1") (pintype "passive"))
      (node (ref "M4") (pin "1") (pinfunction "1_1") (pintype "passive"))
      (node (ref "R6") (pin "1") (pinfunction "1_1") (pintype "passive"))
      (node (ref "S1") (pin "2") (pinfunction "2_2") (pintype "passive"))
    )
    (net (code "58") (name "unconnected-(D7-DO-Pad2)") (class "Default")
      (node (ref "D7") (pin "2") (pinfunction "DO_2") (pintype "passive"))
    )
    (net (code "59") (name "unconnected-(S1-Pad3)") (class "Default")
      (node (ref "S1") (pin "3") (pinfunction "3_3") (pintype "passive+no_connect"))
    )
    (net (code "60") (name "unconnected-(U1-PA0-WKUP-Pad10)") (class "Default")
      (node (ref "U1") (pin "10") (pinfunction "PA0-WKUP_10") (pintype "bidirectional"))
    )
    (net (code "61") (name "unconnected-(U1-PA2-Pad12)") (class "Default")
      (node (ref "U1") (pin "12") (pinfunction "PA2_12") (pintype "bidirectional"))
    )
    (net (code "62") (name "unconnected-(U1-PA3-Pad13)") (class "Default")
      (node (ref "U1") (pin "13") (pinfunction "PA3_13") (pintype "bidirectional"))
    )
    (net (code "63") (name "unconnected-(U1-PA9-Pad30)") (class "Default")
      (node (ref "U1") (pin "30") (pinfunction "PA9_30") (pintype "bidirectional"))
    )
    (net (code "64") (name "unconnected-(U1-PA10-Pad31)") (class "Default")
      (node (ref "U1") (pin "31") (pinfunction "PA10_31") (pintype "bidirectional"))
    )
    (net (code "65") (name "unconnected-(U1-PA11-Pad32)") (class "Default")
      (node (ref "U1") (pin "32") (pinfunction "PA11_32") (pintype "bidirectional"))
    )
    (net (code "66") (name "unconnected-(U1-PA12-Pad33)") (class "Default")
      (node (ref "U1") (pin "33") (pinfunction "PA12_33") (pintype "bidirectional"))
    )
    (net (code "67") (name "unconnected-(U1-PA15{slash}JTDI-Pad38)") (class "Default")
      (node (ref "U1") (pin "38") (pinfunction "PA15/JTDI_38") (pintype "bidirectional"))
    )
    (net (code "68") (name "unconnected-(U1-PB0-Pad18)") (class "Default")
      (node (ref "U1") (pin "18") (pinfunction "PB0_18") (pintype "bidirectional"))
    )
    (net (code "69") (name "unconnected-(U1-PB1-Pad19)") (class "Default")
      (node (ref "U1") (pin "19") (pinfunction "PB1_19") (pintype "bidirectional"))
    )
    (net (code "70") (name "unconnected-(U1-PB3{slash}JTDO-Pad39)") (class "Default")
      (node (ref "U1") (pin "39") (pinfunction "PB3/JTDO_39") (pintype "bidirectional"))
    )
    (net (code "71") (name "unconnected-(U1-PB4{slash}JNTRST-Pad40)") (class "Default")
      (node (ref "U1") (pin "40") (pinfunction "PB4/JNTRST_40") (pintype "bidirectional"))
    )
    (net (code "72") (name "unconnected-(U1-PB10-Pad21)") (class "Default")
      (node (ref "U1") (pin "21") (pinfunction "PB10_21") (pintype "bidirectional"))
    )
    (net (code "73") (name "unconnected-(U1-PB11-Pad22)") (class "Default")
      (node (ref "U1") (pin "22") (pinfunction "PB11_22") (pintype "bidirectional"))
    )
    (net (code "74") (name "unconnected-(U1-PC13-TAMPER-RTC-Pad2)") (class "Default")
      (node (ref "U1") (pin "2") (pinfunction "PC13-TAMPER-RTC_2") (pintype "bidirectional"))
    )
    (net (code "75") (name "unconnected-(U1-PC14-OSC32_IN-Pad3)") (class "Default")
      (node (ref "U1") (pin "3") (pinfunction "PC14-OSC32_IN_3") (pintype "bidirectional"))
    )
    (net (code "76") (name "unconnected-(U1-PC15-OSC32_OUT-Pad4)") (class "Default")
      (node (ref "U1") (pin "4") (pinfunction "PC15-OSC32_OUT_4") (pintype "bidirectional"))
    )
    (net (code "77") (name "unconnected-(U4-A-CL-Pad7)") (class "Default")
      (node (ref "U4") (pin "7") (pinfunction "A-CL_7") (pintype "passive+no_connect"))
    )
    (net (code "78") (name "unconnected-(U4-A_DA-Pad6)") (class "Default")
      (node (ref "U4") (pin "6") (pinfunction "A_DA_6") (pintype "passive+no_connect"))
    )
    (net (code "79") (name "unconnected-(U4-CLKOUT-Pad22)") (class "Default")
      (node (ref "U4") (pin "22") (pinfunction "CLKOUT_22") (pintype "passive+no_connect"))
    )
    (net (code "80") (name "unconnected-(U4-NC-Pad2)") (class "Default")
      (node (ref "U4") (pin "2") (pinfunction "NC_2") (pintype "passive+no_connect"))
    )
    (net (code "81") (name "unconnected-(U4-NC-Pad3)") (class "Default")
      (node (ref "U4") (pin "3") (pinfunction "NC_3") (pintype "passive+no_connect"))
    )
    (net (code "82") (name "unconnected-(U4-NC-Pad4)") (class "Default")
      (node (ref "U4") (pin "4") (pinfunction "NC_4") (pintype "passive+no_connect"))
    )
    (net (code "83") (name "unconnected-(U4-NC-Pad5)") (class "Default")
      (node (ref "U4") (pin "5") (pinfunction "NC_5") (pintype "passive+no_connect"))
    )
    (net (code "84") (name "unconnected-(U4-NC-Pad14)") (class "Default")
      (node (ref "U4") (pin "14") (pinfunction "NC_14") (pintype "passive+no_connect"))
    )
    (net (code "85") (name "unconnected-(U4-NC-Pad15)") (class "Default")
      (node (ref "U4") (pin "15") (pinfunction "NC_15") (pintype "passive+no_connect"))
    )
    (net (code "86") (name "unconnected-(U4-NC-Pad16)") (class "Default")
      (node (ref "U4") (pin "16") (pinfunction "NC_16") (pintype "passive+no_connect"))
    )
    (net (code "87") (name "unconnected-(U4-NC-Pad17)") (class "Default")
      (node (ref "U4") (pin "17") (pinfunction "NC_17") (pintype "passive+no_connect"))
    )
    (net (code "88") (name "unconnected-(U4-RESV-Pad19)") (class "Default")
      (node (ref "U4") (pin "19") (pinfunction "RESV_19") (pintype "passive+no_connect"))
    )
    (net (code "89") (name "unconnected-(U4-RESV-Pad21)") (class "Default")
      (node (ref "U4") (pin "21") (pinfunction "RESV_21") (pintype "passive+no_connect"))
    )
    (net (code "90") (name "unconnected-(X2-GND-Pad2)") (class "Default")
      (node (ref "X2") (pin "2") (pinfunction "GND_2") (pintype "passive+no_connect"))
    )
    (net (code "91") (name "unconnected-(X2-GND-Pad4)") (class "Default")
      (node (ref "X2") (pin "4") (pinfunction "GND_4") (pintype "passive+no_connect"))
    )
  )
)
